# SCH_zafir-project_2024-11-25.net
KiCad netlist of a schematic drawn in EasyEDA
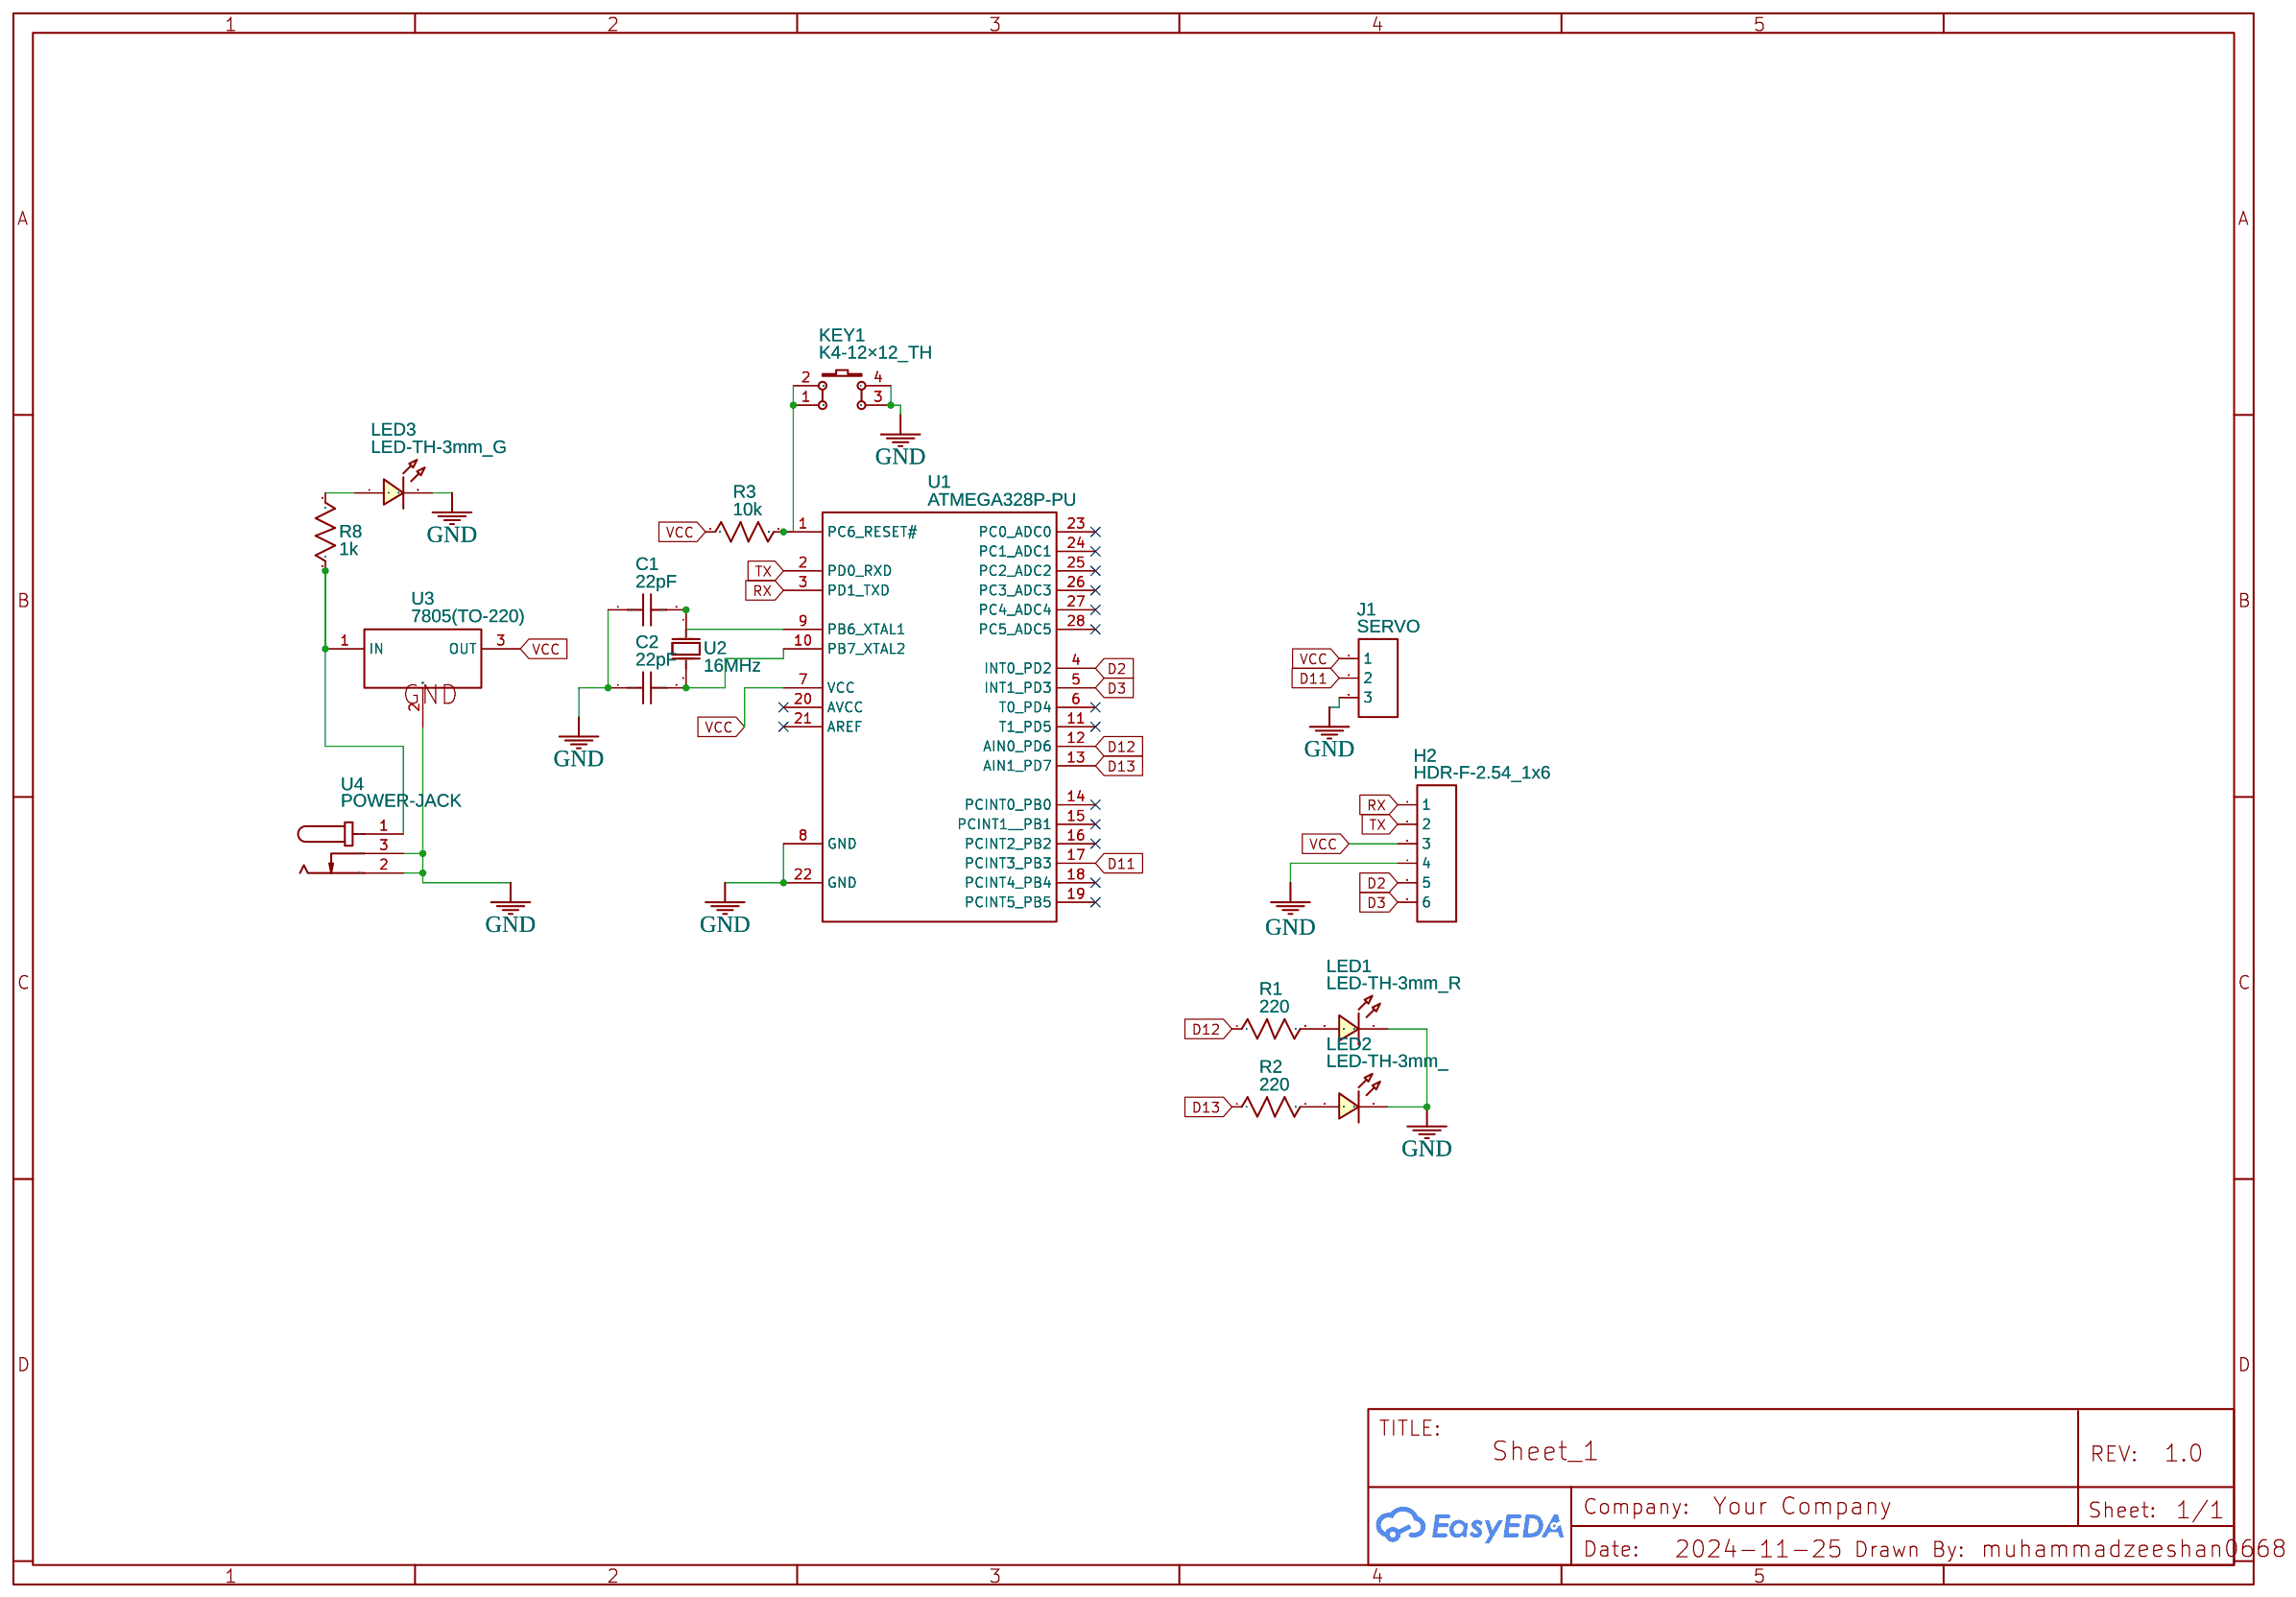
[diagram p0: schematic sheet]

(export (version "E")
  (design (tool "Eeschema 10.0.6"))
  (components
    (comp (ref "C1")
      (value "22pF")
      (fields
        (field (name "Manufacturer Part") "CC1H220KA1EDCH4B1100")
        (field (name "Manufacturer") "Dersonic(德尔创)")
      )
      (libsource (lib "") (part "CC1H220KA1EDCH4B1100"))
    )
    (comp (ref "C2")
      (value "22pF")
      (fields
        (field (name "Manufacturer Part") "CC1H220KA1EDCH4B1100")
        (field (name "Manufacturer") "Dersonic(德尔创)")
      )
      (libsource (lib "") (part "CC1H220KA1EDCH4B1100"))
    )
    (comp (ref "H2") (value "HDR-F-2.54_1x6") (libsource (lib "") (part "HDR-F-2.54_1x6")))
    (comp (ref "J1") (value "SERVO") (libsource (lib "") (part "HDR-M-2.54_1x3")))
    (comp (ref "KEY1")
      (value "K4-12×12_TH")
      (fields (field (name "Manufacturer Part") "K2-1103DP-M4SW-04") (field (name "Manufacturer") "韩国韩荣"))
      (libsource (lib "") (part "K4-12×12_TH"))
    )
    (comp (ref "LED1")
      (value "LED-TH-3mm_R")
      (fields
        (field (name "Manufacturer Part") "204-10SDRD/S530-A3-L")
        (field (name "Manufacturer") "EVERLIGHT(台湾亿光)")
      )
      (libsource (lib "") (part "LED-TH-3mm_R"))
    )
    (comp (ref "LED2")
      (value "LED-TH-3mm_")
      (fields
        (field (name "Manufacturer Part") "204-10SDRD/S530-A3-L")
        (field (name "Manufacturer") "EVERLIGHT(台湾亿光)")
      )
      (libsource (lib "") (part "LED-TH-3mm_R"))
    )
    (comp (ref "LED3")
      (value "LED-TH-3mm_G")
      (fields
        (field (name "Manufacturer Part") "204-10SYGD/S530-E3")
        (field (name "Manufacturer") "EVERLIGHT(台湾亿光)")
      )
      (libsource (lib "") (part "LED-TH-3mm_G"))
    )
    (comp (ref "R1") (value "220") (libsource (lib "") (part "R_AXIAL-0.4_US")))
    (comp (ref "R2") (value "220") (libsource (lib "") (part "R_AXIAL-0.4_US")))
    (comp (ref "R3") (value "10k") (libsource (lib "") (part "R_AXIAL-0.4_US")))
    (comp (ref "R8") (value "1k") (libsource (lib "") (part "R_AXIAL-0.4_US_1")))
    (comp (ref "U1")
      (value "ATMEGA328P-PU")
      (fields (field (name "Manufacturer") "MICROCHIP(美国微芯)"))
      (libsource (lib "") (part "ATMEGA328P-PU"))
    )
    (comp (ref "U2")
      (value "16MHz")
      (fields
        (field (name "Manufacturer Part") "HC49US-FF5F18-6.1440MHZ")
        (field (name "Manufacturer") "ILSI")
      )
      (libsource (lib "") (part "HC49US-FF5F18-6.1440MHZ"))
    )
    (comp (ref "U3")
      (value "7805(TO-220)")
      (fields
        (field (name "Manufacturer Part") "L7805CV-DG")
        (field (name "Manufacturer") "STMicroelectronics")
      )
      (libsource (lib "") (part "7805(TO-220)"))
    )
    (comp (ref "U4")
      (value "POWER-JACK")
      (fields (field (name "Manufacturer") "索峰"))
      (libsource (lib "") (part "POWER-JACK"))
    )
  )
  (nets
    (net (code "1") (name "D2") (class "Default")
      (node (ref "H2") (pin "5") (pinfunction "5_5") (pintype "input"))
      (node (ref "U1") (pin "4") (pinfunction "INT0_PD2_4") (pintype "bidirectional"))
    )
    (net (code "2") (name "D3") (class "Default")
      (node (ref "H2") (pin "6") (pinfunction "6_6") (pintype "input"))
      (node (ref "U1") (pin "5") (pinfunction "INT1_PD3_5") (pintype "bidirectional"))
    )
    (net (code "3") (name "D11") (class "Default")
      (node (ref "J1") (pin "2") (pinfunction "2_2") (pintype "input"))
      (node (ref "U1") (pin "17") (pinfunction "PCINT3_PB3_17") (pintype "bidirectional"))
    )
    (net (code "4") (name "D12") (class "Default")
      (node (ref "R1") (pin "1") (pinfunction "1_1") (pintype "unspecified"))
      (node (ref "U1") (pin "12") (pinfunction "AIN0_PD6_12") (pintype "bidirectional"))
    )
    (net (code "5") (name "D13") (class "Default")
      (node (ref "R2") (pin "1") (pinfunction "1_1") (pintype "unspecified"))
      (node (ref "U1") (pin "13") (pinfunction "AIN1_PD7_13") (pintype "bidirectional"))
    )
    (net (code "6") (name "GND") (class "Default")
      (node (ref "C1") (pin "1") (pinfunction "1_1") (pintype "unspecified"))
      (node (ref "C2") (pin "1") (pinfunction "1_1") (pintype "unspecified"))
      (node (ref "H2") (pin "4") (pinfunction "4_4") (pintype "input"))
      (node (ref "J1") (pin "3") (pinfunction "3_3") (pintype "input"))
      (node (ref "KEY1") (pin "3") (pinfunction "3_3") (pintype "unspecified"))
      (node (ref "KEY1") (pin "4") (pinfunction "4_4") (pintype "unspecified"))
      (node (ref "LED1") (pin "2") (pinfunction "2_2") (pintype "unspecified"))
      (node (ref "LED2") (pin "2") (pinfunction "2_2") (pintype "unspecified"))
      (node (ref "LED3") (pin "2") (pinfunction "2_2") (pintype "unspecified"))
      (node (ref "U1") (pin "22") (pinfunction "GND_22") (pintype "passive"))
      (node (ref "U1") (pin "8") (pinfunction "GND_8") (pintype "passive"))
      (node (ref "U3") (pin "2") (pinfunction "GND_2") (pintype "passive"))
      (node (ref "U4") (pin "2") (pinfunction "2_2") (pintype "unspecified"))
      (node (ref "U4") (pin "3") (pinfunction "3_3") (pintype "unspecified"))
    )
    (net (code "7") (name "Net-(LED1-Pad1)") (class "Default")
      (node (ref "LED1") (pin "1") (pinfunction "1_1") (pintype "unspecified"))
      (node (ref "R1") (pin "2") (pinfunction "2_2") (pintype "unspecified"))
    )
    (net (code "8") (name "Net-(LED2-Pad1)") (class "Default")
      (node (ref "LED2") (pin "1") (pinfunction "1_1") (pintype "unspecified"))
      (node (ref "R2") (pin "2") (pinfunction "2_2") (pintype "unspecified"))
    )
    (net (code "9") (name "Net-(LED3-Pad1)") (class "Default")
      (node (ref "LED3") (pin "1") (pinfunction "1_1") (pintype "unspecified"))
      (node (ref "R8") (pin "2") (pinfunction "2_2") (pintype "unspecified"))
    )
    (net (code "10") (name "Net-(U1-PB6_XTAL1)") (class "Default")
      (node (ref "C1") (pin "2") (pinfunction "2_2") (pintype "unspecified"))
      (node (ref "U1") (pin "9") (pinfunction "PB6_XTAL1_9") (pintype "bidirectional"))
      (node (ref "U2") (pin "1") (pinfunction "1_1") (pintype "input"))
    )
    (net (code "11") (name "Net-(U1-PB7_XTAL2)") (class "Default")
      (node (ref "C2") (pin "2") (pinfunction "2_2") (pintype "unspecified"))
      (node (ref "U1") (pin "10") (pinfunction "PB7_XTAL2_10") (pintype "bidirectional"))
      (node (ref "U2") (pin "2") (pinfunction "2_2") (pintype "input"))
    )
    (net (code "12") (name "Net-(U1-PC6_RESET#)") (class "Default")
      (node (ref "KEY1") (pin "1") (pinfunction "1_1") (pintype "unspecified"))
      (node (ref "KEY1") (pin "2") (pinfunction "2_2") (pintype "unspecified"))
      (node (ref "R3") (pin "2") (pinfunction "2_2") (pintype "unspecified"))
      (node (ref "U1") (pin "1") (pinfunction "PC6_RESET#_1") (pintype "bidirectional"))
    )
    (net (code "13") (name "Net-(U3-IN)") (class "Default")
      (node (ref "R8") (pin "1") (pinfunction "1_1") (pintype "unspecified"))
      (node (ref "U3") (pin "1") (pinfunction "IN_1") (pintype "passive"))
      (node (ref "U4") (pin "1") (pinfunction "1_1") (pintype "unspecified"))
    )
    (net (code "14") (name "RX") (class "Default")
      (node (ref "H2") (pin "1") (pinfunction "1_1") (pintype "input"))
      (node (ref "U1") (pin "3") (pinfunction "PD1_TXD_3") (pintype "bidirectional"))
    )
    (net (code "15") (name "TX") (class "Default")
      (node (ref "H2") (pin "2") (pinfunction "2_2") (pintype "input"))
      (node (ref "U1") (pin "2") (pinfunction "PD0_RXD_2") (pintype "bidirectional"))
    )
    (net (code "16") (name "VCC") (class "Default")
      (node (ref "H2") (pin "3") (pinfunction "3_3") (pintype "input"))
      (node (ref "J1") (pin "1") (pinfunction "1_1") (pintype "input"))
      (node (ref "R3") (pin "1") (pinfunction "1_1") (pintype "unspecified"))
      (node (ref "U1") (pin "7") (pinfunction "VCC_7") (pintype "passive"))
      (node (ref "U3") (pin "3") (pinfunction "OUT_3") (pintype "passive"))
    )
    (net (code "17") (name "unconnected-(U1-AREF-Pad21)") (class "Default")
      (node (ref "U1") (pin "21") (pinfunction "AREF_21") (pintype "passive+no_connect"))
    )
    (net (code "18") (name "unconnected-(U1-AVCC-Pad20)") (class "Default")
      (node (ref "U1") (pin "20") (pinfunction "AVCC_20") (pintype "passive+no_connect"))
    )
    (net (code "19") (name "unconnected-(U1-PC0_ADC0-Pad23)") (class "Default")
      (node (ref "U1") (pin "23") (pinfunction "PC0_ADC0_23") (pintype "bidirectional+no_connect"))
    )
    (net (code "20") (name "unconnected-(U1-PC1_ADC1-Pad24)") (class "Default")
      (node (ref "U1") (pin "24") (pinfunction "PC1_ADC1_24") (pintype "bidirectional+no_connect"))
    )
    (net (code "21") (name "unconnected-(U1-PC2_ADC2-Pad25)") (class "Default")
      (node (ref "U1") (pin "25") (pinfunction "PC2_ADC2_25") (pintype "bidirectional+no_connect"))
    )
    (net (code "22") (name "unconnected-(U1-PC3_ADC3-Pad26)") (class "Default")
      (node (ref "U1") (pin "26") (pinfunction "PC3_ADC3_26") (pintype "bidirectional+no_connect"))
    )
    (net (code "23") (name "unconnected-(U1-PC4_ADC4-Pad27)") (class "Default")
      (node (ref "U1") (pin "27") (pinfunction "PC4_ADC4_27") (pintype "bidirectional+no_connect"))
    )
    (net (code "24") (name "unconnected-(U1-PC5_ADC5-Pad28)") (class "Default")
      (node (ref "U1") (pin "28") (pinfunction "PC5_ADC5_28") (pintype "bidirectional+no_connect"))
    )
    (net (code "25") (name "unconnected-(U1-PCINT0_PB0-Pad14)") (class "Default")
      (node (ref "U1") (pin "14") (pinfunction "PCINT0_PB0_14") (pintype "bidirectional+no_connect"))
    )
    (net (code "26") (name "unconnected-(U1-PCINT1__PB1-Pad15)") (class "Default")
      (node (ref "U1") (pin "15") (pinfunction "PCINT1__PB1_15") (pintype "bidirectional+no_connect"))
    )
    (net (code "27") (name "unconnected-(U1-PCINT2_PB2-Pad16)") (class "Default")
      (node (ref "U1") (pin "16") (pinfunction "PCINT2_PB2_16") (pintype "bidirectional+no_connect"))
    )
    (net (code "28") (name "unconnected-(U1-PCINT4_PB4-Pad18)") (class "Default")
      (node (ref "U1") (pin "18") (pinfunction "PCINT4_PB4_18") (pintype "bidirectional+no_connect"))
    )
    (net (code "29") (name "unconnected-(U1-PCINT5_PB5-Pad19)") (class "Default")
      (node (ref "U1") (pin "19") (pinfunction "PCINT5_PB5_19") (pintype "bidirectional+no_connect"))
    )
    (net (code "30") (name "unconnected-(U1-T0_PD4-Pad6)") (class "Default")
      (node (ref "U1") (pin "6") (pinfunction "T0_PD4_6") (pintype "bidirectional+no_connect"))
    )
    (net (code "31") (name "unconnected-(U1-T1_PD5-Pad11)") (class "Default")
      (node (ref "U1") (pin "11") (pinfunction "T1_PD5_11") (pintype "bidirectional+no_connect"))
    )
  )
)
